# mosaico-dock-schematic.net
KiCad netlist of a schematic drawn in EasyEDA
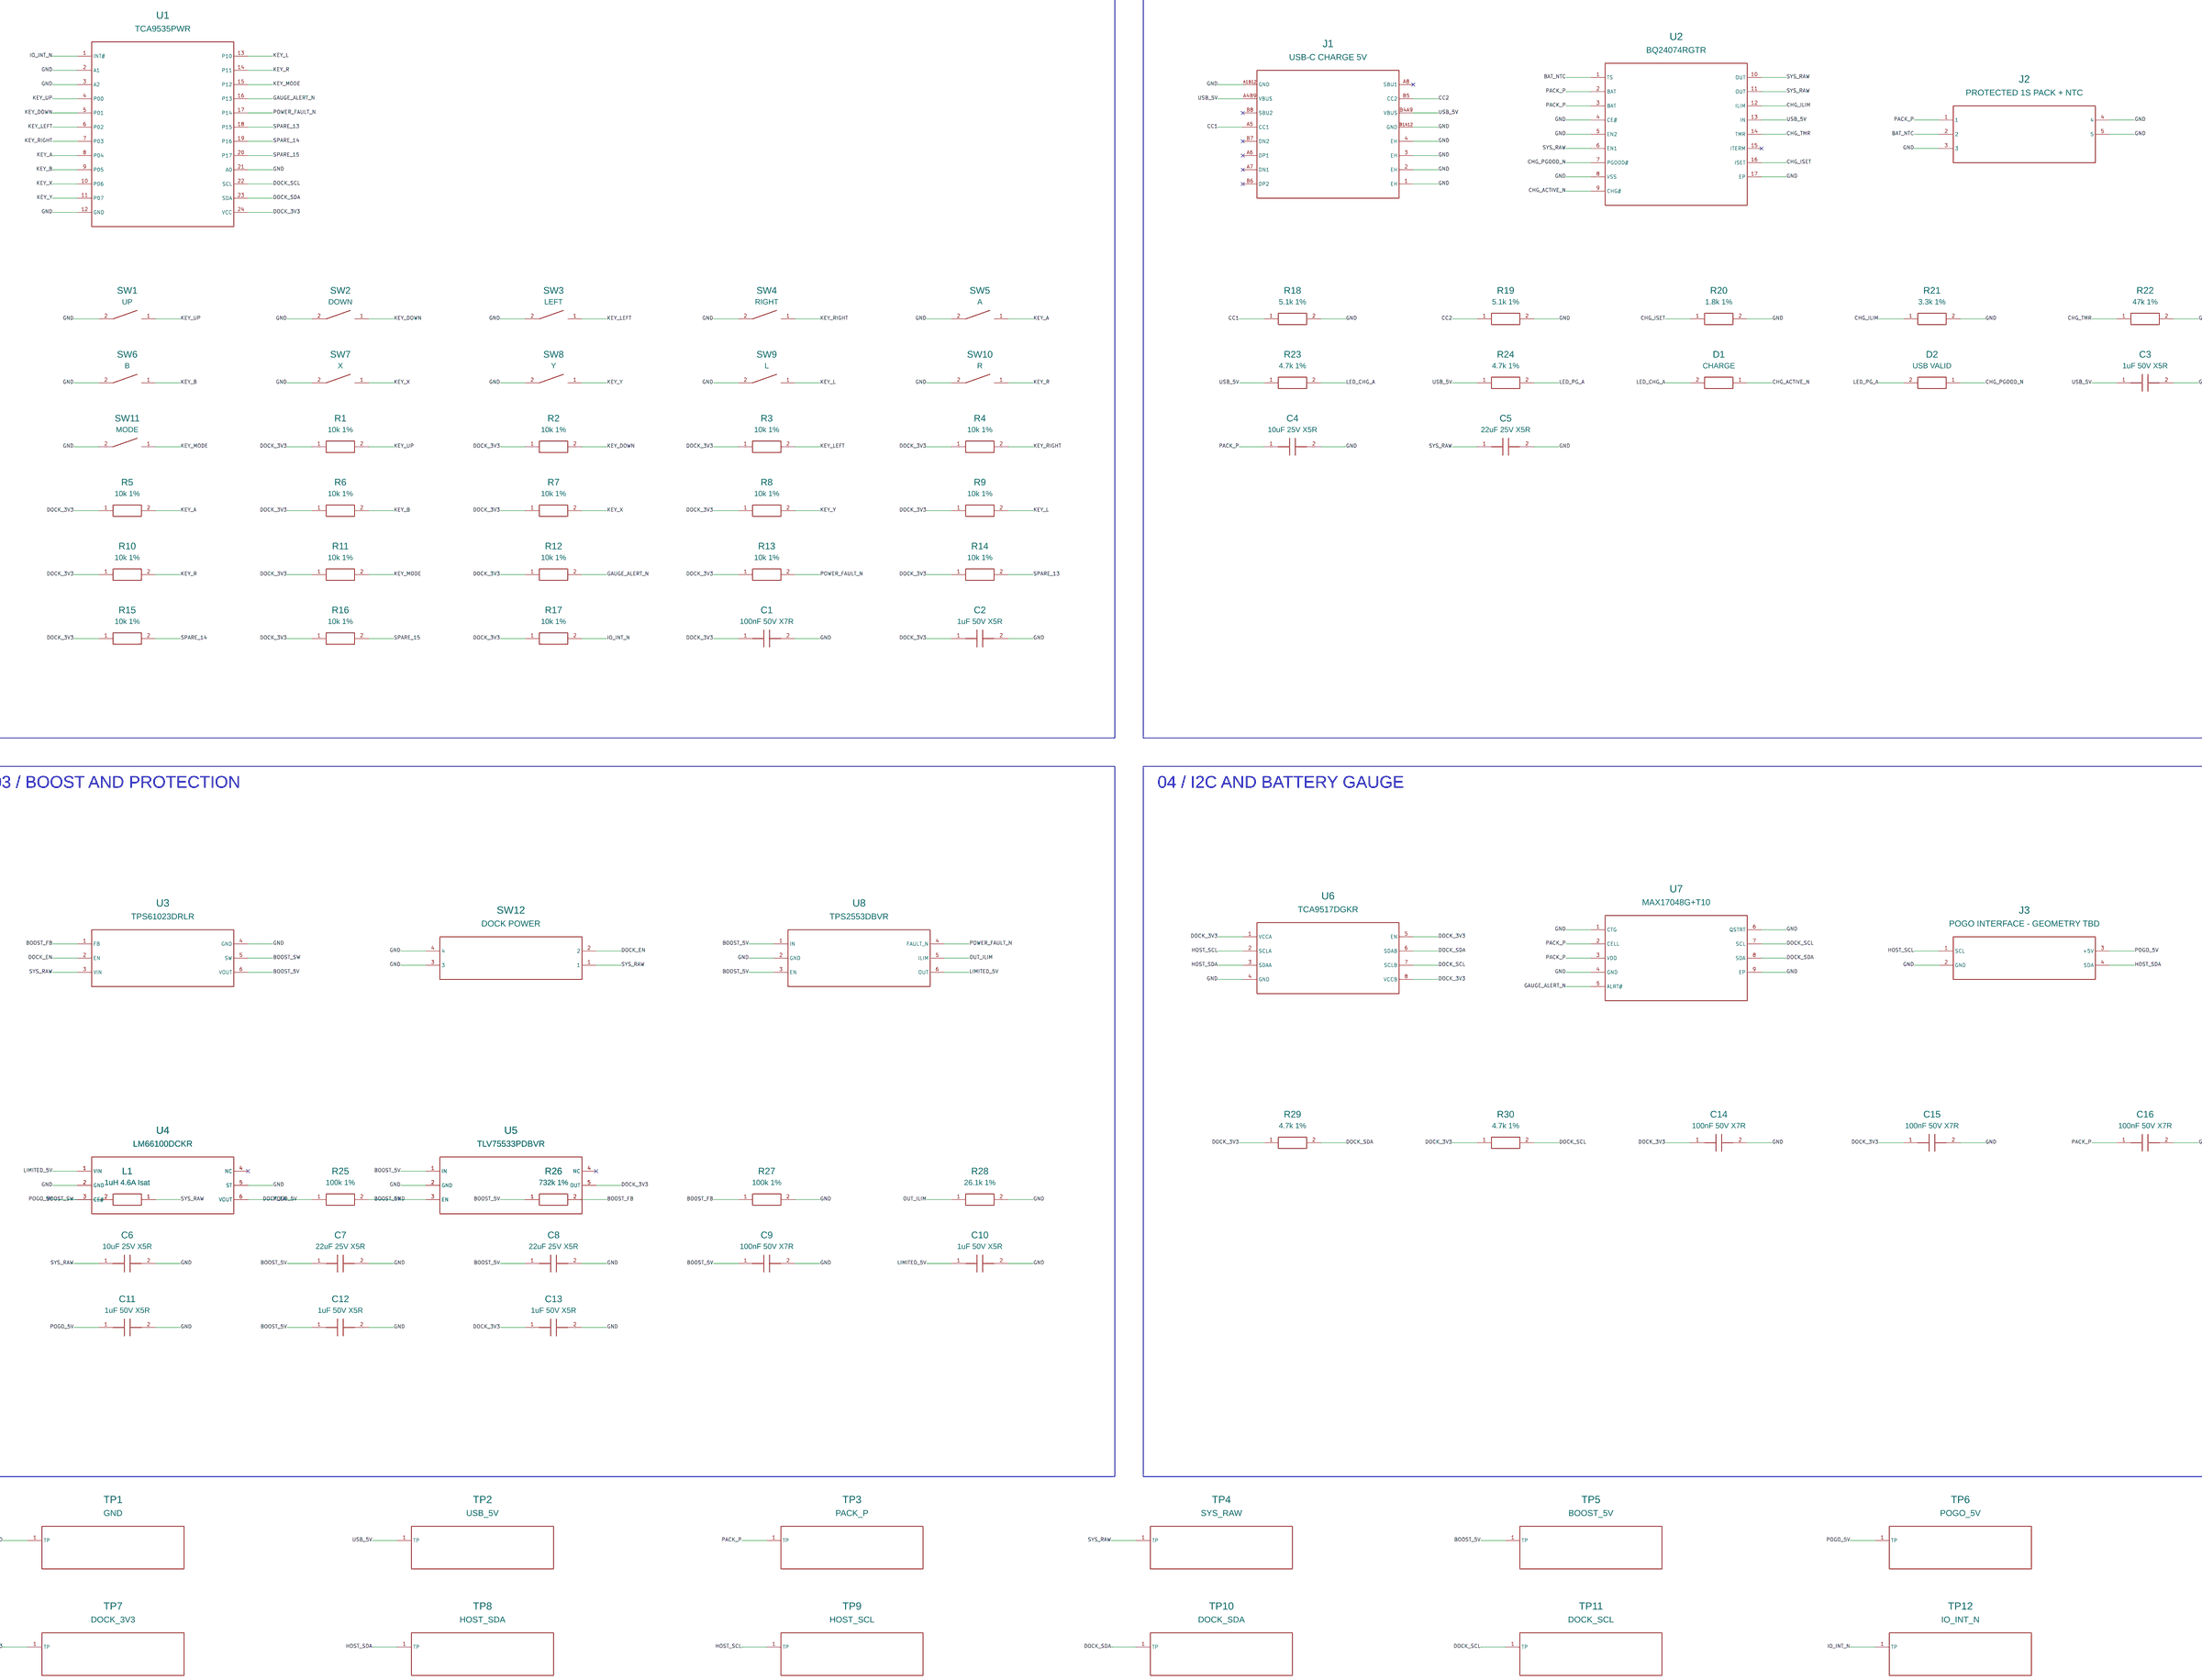
[diagram p0: schematic sheet]

(export (version "E")
  (design (tool "Eeschema 10.0.6"))
  (components
    (comp (ref "C1") (value "100nF 50V X7R") (libsource (lib "") (part "100nF 50V X7R")))
    (comp (ref "C2")
      (value "1uF 50V X5R")
      (fields
        (field (name "Manufacturer Part") "CL10A105KB8NNNC")
        (field (name "Manufacturer") "SAMSUNG(三星)")
      )
      (libsource (lib "") (part "1uF 50V X5R"))
    )
    (comp (ref "C3")
      (value "1uF 50V X5R")
      (fields
        (field (name "Manufacturer Part") "CL10A105KB8NNNC")
        (field (name "Manufacturer") "SAMSUNG(三星)")
      )
      (libsource (lib "") (part "1uF 50V X5R"))
    )
    (comp (ref "C4")
      (value "10uF 25V X5R")
      (fields
        (field (name "Manufacturer Part") "CL10A106MA8NRNC")
        (field (name "Manufacturer") "SAMSUNG(三星)")
      )
      (libsource (lib "") (part "10uF 25V X5R"))
    )
    (comp (ref "C5") (value "22uF 25V X5R") (libsource (lib "") (part "22uF 25V X5R")))
    (comp (ref "C6")
      (value "10uF 25V X5R")
      (fields
        (field (name "Manufacturer Part") "CL10A106MA8NRNC")
        (field (name "Manufacturer") "SAMSUNG(三星)")
      )
      (libsource (lib "") (part "10uF 25V X5R"))
    )
    (comp (ref "C7") (value "22uF 25V X5R") (libsource (lib "") (part "22uF 25V X5R")))
    (comp (ref "C8") (value "22uF 25V X5R") (libsource (lib "") (part "22uF 25V X5R")))
    (comp (ref "C9") (value "100nF 50V X7R") (libsource (lib "") (part "100nF 50V X7R")))
    (comp (ref "C10")
      (value "1uF 50V X5R")
      (fields
        (field (name "Manufacturer Part") "CL10A105KB8NNNC")
        (field (name "Manufacturer") "SAMSUNG(三星)")
      )
      (libsource (lib "") (part "1uF 50V X5R"))
    )
    (comp (ref "C11")
      (value "1uF 50V X5R")
      (fields
        (field (name "Manufacturer Part") "CL10A105KB8NNNC")
        (field (name "Manufacturer") "SAMSUNG(三星)")
      )
      (libsource (lib "") (part "1uF 50V X5R"))
    )
    (comp (ref "C12")
      (value "1uF 50V X5R")
      (fields
        (field (name "Manufacturer Part") "CL10A105KB8NNNC")
        (field (name "Manufacturer") "SAMSUNG(三星)")
      )
      (libsource (lib "") (part "1uF 50V X5R"))
    )
    (comp (ref "C13")
      (value "1uF 50V X5R")
      (fields
        (field (name "Manufacturer Part") "CL10A105KB8NNNC")
        (field (name "Manufacturer") "SAMSUNG(三星)")
      )
      (libsource (lib "") (part "1uF 50V X5R"))
    )
    (comp (ref "C14") (value "100nF 50V X7R") (libsource (lib "") (part "100nF 50V X7R")))
    (comp (ref "C15") (value "100nF 50V X7R") (libsource (lib "") (part "100nF 50V X7R")))
    (comp (ref "C16") (value "100nF 50V X7R") (libsource (lib "") (part "100nF 50V X7R")))
    (comp (ref "D1")
      (value "CHARGE")
      (fields (field (name "Manufacturer Part") "KT-0805黄灯") (field (name "Manufacturer") "KENTO"))
      (libsource (lib "") (part "CHARGE"))
    )
    (comp (ref "D2")
      (value "USB VALID")
      (fields (field (name "Manufacturer Part") "KT-0805黄灯") (field (name "Manufacturer") "KENTO"))
      (libsource (lib "") (part "USB VALID"))
    )
    (comp (ref "J1")
      (value "USB-C CHARGE 5V")
      (fields (field (name "Manufacturer Part") "TYPE-C-31-M-12") (field (name "Manufacturer") "韩国韩荣"))
      (libsource (lib "") (part "USB-C CHARGE 5V"))
    )
    (comp (ref "J2")
      (value "PROTECTED 1S PACK + NTC")
      (fields (field (name "Manufacturer Part") "B3B-PH-SM4-TB(LF)(SN)") (field (name "Manufacturer") "JST"))
      (libsource (lib "") (part "PROTECTED 1S PACK + NTC"))
    )
    (comp (ref "J3")
      (value "POGO INTERFACE - GEOMETRY TBD")
      (libsource (lib "") (part "POGO INTERFACE - GEOMETRY TBD"))
    )
    (comp (ref "L1")
      (value "1uH 4.6A Isat")
      (fields
        (field (name "Manufacturer Part") "FTC201610S1R0MBCA")
        (field (name "Manufacturer") "cjiang(长江微电)")
      )
      (libsource (lib "") (part "1uH 4.6A Isat"))
    )
    (comp (ref "R1")
      (value "10k 1%")
      (fields
        (field (name "Manufacturer Part") "0603WAF1002T5E")
        (field (name "Manufacturer") "UNI-ROYAL(厚声)")
      )
      (libsource (lib "") (part "10k 1%"))
    )
    (comp (ref "R2")
      (value "10k 1%")
      (fields
        (field (name "Manufacturer Part") "0603WAF1002T5E")
        (field (name "Manufacturer") "UNI-ROYAL(厚声)")
      )
      (libsource (lib "") (part "10k 1%"))
    )
    (comp (ref "R3")
      (value "10k 1%")
      (fields
        (field (name "Manufacturer Part") "0603WAF1002T5E")
        (field (name "Manufacturer") "UNI-ROYAL(厚声)")
      )
      (libsource (lib "") (part "10k 1%"))
    )
    (comp (ref "R4")
      (value "10k 1%")
      (fields
        (field (name "Manufacturer Part") "0603WAF1002T5E")
        (field (name "Manufacturer") "UNI-ROYAL(厚声)")
      )
      (libsource (lib "") (part "10k 1%"))
    )
    (comp (ref "R5")
      (value "10k 1%")
      (fields
        (field (name "Manufacturer Part") "0603WAF1002T5E")
        (field (name "Manufacturer") "UNI-ROYAL(厚声)")
      )
      (libsource (lib "") (part "10k 1%"))
    )
    (comp (ref "R6")
      (value "10k 1%")
      (fields
        (field (name "Manufacturer Part") "0603WAF1002T5E")
        (field (name "Manufacturer") "UNI-ROYAL(厚声)")
      )
      (libsource (lib "") (part "10k 1%"))
    )
    (comp (ref "R7")
      (value "10k 1%")
      (fields
        (field (name "Manufacturer Part") "0603WAF1002T5E")
        (field (name "Manufacturer") "UNI-ROYAL(厚声)")
      )
      (libsource (lib "") (part "10k 1%"))
    )
    (comp (ref "R8")
      (value "10k 1%")
      (fields
        (field (name "Manufacturer Part") "0603WAF1002T5E")
        (field (name "Manufacturer") "UNI-ROYAL(厚声)")
      )
      (libsource (lib "") (part "10k 1%"))
    )
    (comp (ref "R9")
      (value "10k 1%")
      (fields
        (field (name "Manufacturer Part") "0603WAF1002T5E")
        (field (name "Manufacturer") "UNI-ROYAL(厚声)")
      )
      (libsource (lib "") (part "10k 1%"))
    )
    (comp (ref "R10")
      (value "10k 1%")
      (fields
        (field (name "Manufacturer Part") "0603WAF1002T5E")
        (field (name "Manufacturer") "UNI-ROYAL(厚声)")
      )
      (libsource (lib "") (part "10k 1%"))
    )
    (comp (ref "R11")
      (value "10k 1%")
      (fields
        (field (name "Manufacturer Part") "0603WAF1002T5E")
        (field (name "Manufacturer") "UNI-ROYAL(厚声)")
      )
      (libsource (lib "") (part "10k 1%"))
    )
    (comp (ref "R12")
      (value "10k 1%")
      (fields
        (field (name "Manufacturer Part") "0603WAF1002T5E")
        (field (name "Manufacturer") "UNI-ROYAL(厚声)")
      )
      (libsource (lib "") (part "10k 1%"))
    )
    (comp (ref "R13")
      (value "10k 1%")
      (fields
        (field (name "Manufacturer Part") "0603WAF1002T5E")
        (field (name "Manufacturer") "UNI-ROYAL(厚声)")
      )
      (libsource (lib "") (part "10k 1%"))
    )
    (comp (ref "R14")
      (value "10k 1%")
      (fields
        (field (name "Manufacturer Part") "0603WAF1002T5E")
        (field (name "Manufacturer") "UNI-ROYAL(厚声)")
      )
      (libsource (lib "") (part "10k 1%"))
    )
    (comp (ref "R15")
      (value "10k 1%")
      (fields
        (field (name "Manufacturer Part") "0603WAF1002T5E")
        (field (name "Manufacturer") "UNI-ROYAL(厚声)")
      )
      (libsource (lib "") (part "10k 1%"))
    )
    (comp (ref "R16")
      (value "10k 1%")
      (fields
        (field (name "Manufacturer Part") "0603WAF1002T5E")
        (field (name "Manufacturer") "UNI-ROYAL(厚声)")
      )
      (libsource (lib "") (part "10k 1%"))
    )
    (comp (ref "R17")
      (value "10k 1%")
      (fields
        (field (name "Manufacturer Part") "0603WAF1002T5E")
        (field (name "Manufacturer") "UNI-ROYAL(厚声)")
      )
      (libsource (lib "") (part "10k 1%"))
    )
    (comp (ref "R18")
      (value "5.1k 1%")
      (fields
        (field (name "Manufacturer Part") "0603WAF5101T5E")
        (field (name "Manufacturer") "UNI-ROYAL(厚声)")
      )
      (libsource (lib "") (part "5.1k 1%"))
    )
    (comp (ref "R19")
      (value "5.1k 1%")
      (fields
        (field (name "Manufacturer Part") "0603WAF5101T5E")
        (field (name "Manufacturer") "UNI-ROYAL(厚声)")
      )
      (libsource (lib "") (part "5.1k 1%"))
    )
    (comp (ref "R20") (value "1.8k 1%") (libsource (lib "") (part "1.8k 1%")))
    (comp (ref "R21") (value "3.3k 1%") (libsource (lib "") (part "3.3k 1%")))
    (comp (ref "R22") (value "47k 1%") (libsource (lib "") (part "47k 1%")))
    (comp (ref "R23")
      (value "4.7k 1%")
      (fields
        (field (name "Manufacturer Part") "0603WAF4701T5E")
        (field (name "Manufacturer") "UNI-ROYAL(厚声)")
      )
      (libsource (lib "") (part "4.7k 1%"))
    )
    (comp (ref "R24")
      (value "4.7k 1%")
      (fields
        (field (name "Manufacturer Part") "0603WAF4701T5E")
        (field (name "Manufacturer") "UNI-ROYAL(厚声)")
      )
      (libsource (lib "") (part "4.7k 1%"))
    )
    (comp (ref "R25")
      (value "100k 1%")
      (fields
        (field (name "Manufacturer Part") "0603WAF1003T5E")
        (field (name "Manufacturer") "UNI-ROYAL(厚声)")
      )
      (libsource (lib "") (part "100k 1%"))
    )
    (comp (ref "R26") (value "732k 1%") (libsource (lib "") (part "732k 1%")))
    (comp (ref "R27")
      (value "100k 1%")
      (fields
        (field (name "Manufacturer Part") "0603WAF1003T5E")
        (field (name "Manufacturer") "UNI-ROYAL(厚声)")
      )
      (libsource (lib "") (part "100k 1%"))
    )
    (comp (ref "R28") (value "26.1k 1%") (libsource (lib "") (part "26.1k 1%")))
    (comp (ref "R29")
      (value "4.7k 1%")
      (fields
        (field (name "Manufacturer Part") "0603WAF4701T5E")
        (field (name "Manufacturer") "UNI-ROYAL(厚声)")
      )
      (libsource (lib "") (part "4.7k 1%"))
    )
    (comp (ref "R30")
      (value "4.7k 1%")
      (fields
        (field (name "Manufacturer Part") "0603WAF4701T5E")
        (field (name "Manufacturer") "UNI-ROYAL(厚声)")
      )
      (libsource (lib "") (part "4.7k 1%"))
    )
    (comp (ref "SW1")
      (value "UP")
      (fields (field (name "Manufacturer Part") "TS-1088-AR02016") (field (name "Manufacturer") "XUNPU(讯普)"))
      (libsource (lib "") (part "UP"))
    )
    (comp (ref "SW2")
      (value "DOWN")
      (fields (field (name "Manufacturer Part") "TS-1088-AR02016") (field (name "Manufacturer") "XUNPU(讯普)"))
      (libsource (lib "") (part "DOWN"))
    )
    (comp (ref "SW3")
      (value "LEFT")
      (fields (field (name "Manufacturer Part") "TS-1088-AR02016") (field (name "Manufacturer") "XUNPU(讯普)"))
      (libsource (lib "") (part "LEFT"))
    )
    (comp (ref "SW4")
      (value "RIGHT")
      (fields (field (name "Manufacturer Part") "TS-1088-AR02016") (field (name "Manufacturer") "XUNPU(讯普)"))
      (libsource (lib "") (part "RIGHT"))
    )
    (comp (ref "SW5")
      (value "A")
      (fields (field (name "Manufacturer Part") "TS-1088-AR02016") (field (name "Manufacturer") "XUNPU(讯普)"))
      (libsource (lib "") (part "A"))
    )
    (comp (ref "SW6")
      (value "B")
      (fields (field (name "Manufacturer Part") "TS-1088-AR02016") (field (name "Manufacturer") "XUNPU(讯普)"))
      (libsource (lib "") (part "B"))
    )
    (comp (ref "SW7")
      (value "X")
      (fields (field (name "Manufacturer Part") "TS-1088-AR02016") (field (name "Manufacturer") "XUNPU(讯普)"))
      (libsource (lib "") (part "X"))
    )
    (comp (ref "SW8")
      (value "Y")
      (fields (field (name "Manufacturer Part") "TS-1088-AR02016") (field (name "Manufacturer") "XUNPU(讯普)"))
      (libsource (lib "") (part "Y"))
    )
    (comp (ref "SW9")
      (value "L")
      (fields (field (name "Manufacturer Part") "TS-1088-AR02016") (field (name "Manufacturer") "XUNPU(讯普)"))
      (libsource (lib "") (part "L"))
    )
    (comp (ref "SW10")
      (value "R")
      (fields (field (name "Manufacturer Part") "TS-1088-AR02016") (field (name "Manufacturer") "XUNPU(讯普)"))
      (libsource (lib "") (part "R"))
    )
    (comp (ref "SW11")
      (value "MODE")
      (fields (field (name "Manufacturer Part") "TS-1088-AR02016") (field (name "Manufacturer") "XUNPU(讯普)"))
      (libsource (lib "") (part "MODE"))
    )
    (comp (ref "SW12")
      (value "DOCK POWER")
      (fields (field (name "Manufacturer Part") "MSK12C02") (field (name "Manufacturer") "SHOU HAN(首韩)"))
      (libsource (lib "") (part "DOCK POWER"))
    )
    (comp (ref "TP1") (value "GND") (libsource (lib "") (part "GND")))
    (comp (ref "TP2") (value "USB_5V") (libsource (lib "") (part "USB_5V")))
    (comp (ref "TP3") (value "PACK_P") (libsource (lib "") (part "PACK_P")))
    (comp (ref "TP4") (value "SYS_RAW") (libsource (lib "") (part "SYS_RAW")))
    (comp (ref "TP5") (value "BOOST_5V") (libsource (lib "") (part "BOOST_5V")))
    (comp (ref "TP6") (value "POGO_5V") (libsource (lib "") (part "POGO_5V")))
    (comp (ref "TP7") (value "DOCK_3V3") (libsource (lib "") (part "DOCK_3V3")))
    (comp (ref "TP8") (value "HOST_SDA") (libsource (lib "") (part "HOST_SDA")))
    (comp (ref "TP9") (value "HOST_SCL") (libsource (lib "") (part "HOST_SCL")))
    (comp (ref "TP10") (value "DOCK_SDA") (libsource (lib "") (part "DOCK_SDA")))
    (comp (ref "TP11") (value "DOCK_SCL") (libsource (lib "") (part "DOCK_SCL")))
    (comp (ref "TP12") (value "IO_INT_N") (libsource (lib "") (part "IO_INT_N")))
    (comp (ref "U1")
      (value "TCA9535PWR")
      (fields (field (name "Manufacturer") "TI(德州仪器)"))
      (libsource (lib "") (part "TCA9535PWR"))
    )
    (comp (ref "U2")
      (value "BQ24074RGTR")
      (fields (field (name "Manufacturer") "TI(德州仪器)"))
      (libsource (lib "") (part "BQ24074RGTR"))
    )
    (comp (ref "U3")
      (value "TPS61023DRLR")
      (fields (field (name "Manufacturer") "TI(德州仪器)"))
      (libsource (lib "") (part "TPS61023DRLR"))
    )
    (comp (ref "U4")
      (value "LM66100DCKR")
      (fields (field (name "Manufacturer") "TI(德州仪器)"))
      (libsource (lib "") (part "LM66100DCKR"))
    )
    (comp (ref "U5")
      (value "TLV75533PDBVR")
      (fields (field (name "Manufacturer") "TI(德州仪器)"))
      (libsource (lib "") (part "TLV75533PDBVR"))
    )
    (comp (ref "U6")
      (value "TCA9517DGKR")
      (fields (field (name "Manufacturer") "TI(德州仪器)"))
      (libsource (lib "") (part "TCA9517DGKR"))
    )
    (comp (ref "U7")
      (value "MAX17048G+T10")
      (fields (field (name "Manufacturer") "ADI(亚德诺)/MAXIM(美信)"))
      (libsource (lib "") (part "MAX17048G+T10"))
    )
    (comp (ref "U8") (value "TPS2553DBVR") (libsource (lib "") (part "TPS2553DBVR")))
  )
  (nets
    (net (code "1") (name "/BAT_NTC") (class "Default")
      (node (ref "J2") (pin "2") (pinfunction "2_2") (pintype "unspecified"))
      (node (ref "U2") (pin "1") (pinfunction "TS_1") (pintype "unspecified"))
    )
    (net (code "2") (name "/BOOST_5V") (class "Default")
      (node (ref "C12") (pin "1") (pintype "unspecified"))
      (node (ref "C7") (pin "1") (pintype "unspecified"))
      (node (ref "C8") (pin "1") (pintype "unspecified"))
      (node (ref "C9") (pin "1") (pintype "unspecified"))
      (node (ref "R26") (pin "1") (pintype "unspecified"))
      (node (ref "TP5") (pin "1") (pinfunction "TP_1") (pintype "unspecified"))
      (node (ref "U3") (pin "6") (pinfunction "VOUT_6") (pintype "unspecified"))
      (node (ref "U5") (pin "1") (pinfunction "IN_1") (pintype "unspecified"))
      (node (ref "U5") (pin "3") (pinfunction "EN_3") (pintype "unspecified"))
      (node (ref "U8") (pin "1") (pinfunction "IN_1") (pintype "unspecified"))
      (node (ref "U8") (pin "3") (pinfunction "EN_3") (pintype "unspecified"))
    )
    (net (code "3") (name "/BOOST_FB") (class "Default")
      (node (ref "R26") (pin "2") (pintype "unspecified"))
      (node (ref "R27") (pin "1") (pintype "unspecified"))
      (node (ref "U3") (pin "1") (pinfunction "FB_1") (pintype "unspecified"))
    )
    (net (code "4") (name "/BOOST_SW") (class "Default")
      (node (ref "C11") (pin "1") (pintype "unspecified"))
      (node (ref "J3") (pin "3") (pinfunction "+5V_3") (pintype "unspecified"))
      (node (ref "L1") (pin "2") (pintype "unspecified"))
      (node (ref "TP6") (pin "1") (pinfunction "TP_1") (pintype "unspecified"))
      (node (ref "U3") (pin "5") (pinfunction "SW_5") (pintype "unspecified"))
      (node (ref "U4") (pin "3") (pinfunction "CE#_3") (pintype "unspecified"))
      (node (ref "U4") (pin "6") (pinfunction "VOUT_6") (pintype "unspecified"))
    )
    (net (code "5") (name "/CC1") (class "Default")
      (node (ref "J1") (pin "A5") (pinfunction "CC1_A5") (pintype "unspecified"))
      (node (ref "R18") (pin "1") (pintype "unspecified"))
    )
    (net (code "6") (name "/CC2") (class "Default")
      (node (ref "J1") (pin "B5") (pinfunction "CC2_B5") (pintype "unspecified"))
      (node (ref "R19") (pin "1") (pintype "unspecified"))
    )
    (net (code "7") (name "/CHG_ACTIVE_N") (class "Default")
      (node (ref "D1") (pin "1") (pintype "unspecified"))
      (node (ref "U2") (pin "9") (pinfunction "CHG#_9") (pintype "unspecified"))
    )
    (net (code "8") (name "/CHG_ILIM") (class "Default")
      (node (ref "R21") (pin "1") (pintype "unspecified"))
      (node (ref "U2") (pin "12") (pinfunction "ILIM_12") (pintype "unspecified"))
    )
    (net (code "9") (name "/CHG_ISET") (class "Default")
      (node (ref "R20") (pin "1") (pintype "unspecified"))
      (node (ref "U2") (pin "16") (pinfunction "ISET_16") (pintype "unspecified"))
    )
    (net (code "10") (name "/CHG_PGOOD_N") (class "Default")
      (node (ref "D2") (pin "1") (pintype "unspecified"))
      (node (ref "U2") (pin "7") (pinfunction "PGOOD#_7") (pintype "unspecified"))
    )
    (net (code "11") (name "/CHG_TMR") (class "Default")
      (node (ref "R22") (pin "1") (pintype "unspecified"))
      (node (ref "U2") (pin "14") (pinfunction "TMR_14") (pintype "unspecified"))
    )
    (net (code "12") (name "/DOCK_3V3") (class "Default")
      (node (ref "C1") (pin "1") (pintype "unspecified"))
      (node (ref "C13") (pin "1") (pintype "unspecified"))
      (node (ref "C14") (pin "1") (pintype "unspecified"))
      (node (ref "C15") (pin "1") (pintype "unspecified"))
      (node (ref "C2") (pin "1") (pintype "unspecified"))
      (node (ref "R1") (pin "1") (pintype "unspecified"))
      (node (ref "R10") (pin "1") (pintype "unspecified"))
      (node (ref "R11") (pin "1") (pintype "unspecified"))
      (node (ref "R12") (pin "1") (pintype "unspecified"))
      (node (ref "R13") (pin "1") (pintype "unspecified"))
      (node (ref "R14") (pin "1") (pintype "unspecified"))
      (node (ref "R15") (pin "1") (pintype "unspecified"))
      (node (ref "R16") (pin "1") (pintype "unspecified"))
      (node (ref "R17") (pin "1") (pintype "unspecified"))
      (node (ref "R2") (pin "1") (pintype "unspecified"))
      (node (ref "R29") (pin "1") (pintype "unspecified"))
      (node (ref "R3") (pin "1") (pintype "unspecified"))
      (node (ref "R30") (pin "1") (pintype "unspecified"))
      (node (ref "R4") (pin "1") (pintype "unspecified"))
      (node (ref "R5") (pin "1") (pintype "unspecified"))
      (node (ref "R6") (pin "1") (pintype "unspecified"))
      (node (ref "R7") (pin "1") (pintype "unspecified"))
      (node (ref "R8") (pin "1") (pintype "unspecified"))
      (node (ref "R9") (pin "1") (pintype "unspecified"))
      (node (ref "TP7") (pin "1") (pinfunction "TP_1") (pintype "unspecified"))
      (node (ref "U1") (pin "24") (pinfunction "VCC_24") (pintype "unspecified"))
      (node (ref "U5") (pin "5") (pinfunction "OUT_5") (pintype "unspecified"))
      (node (ref "U6") (pin "1") (pinfunction "VCCA_1") (pintype "unspecified"))
      (node (ref "U6") (pin "5") (pinfunction "EN_5") (pintype "unspecified"))
      (node (ref "U6") (pin "8") (pinfunction "VCCB_8") (pintype "unspecified"))
    )
    (net (code "13") (name "/DOCK_EN") (class "Default")
      (node (ref "R25") (pin "1") (pintype "unspecified"))
      (node (ref "SW12") (pin "2") (pinfunction "2_2") (pintype "unspecified"))
      (node (ref "U3") (pin "2") (pinfunction "EN_2") (pintype "unspecified"))
    )
    (net (code "14") (name "/DOCK_SCL") (class "Default")
      (node (ref "R30") (pin "2") (pintype "unspecified"))
      (node (ref "TP11") (pin "1") (pinfunction "TP_1") (pintype "unspecified"))
      (node (ref "U1") (pin "22") (pinfunction "SCL_22") (pintype "unspecified"))
      (node (ref "U6") (pin "7") (pinfunction "SCLB_7") (pintype "unspecified"))
      (node (ref "U7") (pin "7") (pinfunction "SCL_7") (pintype "unspecified"))
    )
    (net (code "15") (name "/DOCK_SDA") (class "Default")
      (node (ref "R29") (pin "2") (pintype "unspecified"))
      (node (ref "TP10") (pin "1") (pinfunction "TP_1") (pintype "unspecified"))
      (node (ref "U1") (pin "23") (pinfunction "SDA_23") (pintype "unspecified"))
      (node (ref "U6") (pin "6") (pinfunction "SDAB_6") (pintype "unspecified"))
      (node (ref "U7") (pin "8") (pinfunction "SDA_8") (pintype "unspecified"))
    )
    (net (code "16") (name "/GAUGE_ALERT_N") (class "Default")
      (node (ref "R12") (pin "2") (pintype "unspecified"))
      (node (ref "U1") (pin "16") (pinfunction "P13_16") (pintype "unspecified"))
      (node (ref "U7") (pin "5") (pinfunction "ALRT#_5") (pintype "unspecified"))
    )
    (net (code "17") (name "/GND") (class "Default")
      (node (ref "C1") (pin "2") (pintype "unspecified"))
      (node (ref "C10") (pin "2") (pintype "unspecified"))
      (node (ref "C11") (pin "2") (pintype "unspecified"))
      (node (ref "C12") (pin "2") (pintype "unspecified"))
      (node (ref "C13") (pin "2") (pintype "unspecified"))
      (node (ref "C14") (pin "2") (pintype "unspecified"))
      (node (ref "C15") (pin "2") (pintype "unspecified"))
      (node (ref "C16") (pin "2") (pintype "unspecified"))
      (node (ref "C2") (pin "2") (pintype "unspecified"))
      (node (ref "C3") (pin "2") (pintype "unspecified"))
      (node (ref "C4") (pin "2") (pintype "unspecified"))
      (node (ref "C5") (pin "2") (pintype "unspecified"))
      (node (ref "C6") (pin "2") (pintype "unspecified"))
      (node (ref "C7") (pin "2") (pintype "unspecified"))
      (node (ref "C8") (pin "2") (pintype "unspecified"))
      (node (ref "C9") (pin "2") (pintype "unspecified"))
      (node (ref "J1") (pin "1") (pinfunction "EH_1") (pintype "unspecified"))
      (node (ref "J1") (pin "2") (pinfunction "EH_2") (pintype "unspecified"))
      (node (ref "J1") (pin "3") (pinfunction "EH_3") (pintype "unspecified"))
      (node (ref "J1") (pin "4") (pinfunction "EH_4") (pintype "unspecified"))
      (node (ref "J1") (pin "A1B12") (pinfunction "GND_A1B12") (pintype "unspecified"))
      (node (ref "J1") (pin "B1A12") (pinfunction "GND_B1A12") (pintype "unspecified"))
      (node (ref "J2") (pin "3") (pinfunction "3_3") (pintype "unspecified"))
      (node (ref "J2") (pin "4") (pinfunction "4_4") (pintype "unspecified"))
      (node (ref "J2") (pin "5") (pinfunction "5_5") (pintype "unspecified"))
      (node (ref "J3") (pin "2") (pinfunction "GND_2") (pintype "unspecified"))
      (node (ref "R18") (pin "2") (pintype "unspecified"))
      (node (ref "R19") (pin "2") (pintype "unspecified"))
      (node (ref "R20") (pin "2") (pintype "unspecified"))
      (node (ref "R21") (pin "2") (pintype "unspecified"))
      (node (ref "R22") (pin "2") (pintype "unspecified"))
      (node (ref "R25") (pin "2") (pintype "unspecified"))
      (node (ref "R27") (pin "2") (pintype "unspecified"))
      (node (ref "R28") (pin "2") (pintype "unspecified"))
      (node (ref "SW1") (pin "2") (pintype "unspecified"))
      (node (ref "SW10") (pin "2") (pintype "unspecified"))
      (node (ref "SW11") (pin "2") (pintype "unspecified"))
      (node (ref "SW12") (pin "3") (pinfunction "3_3") (pintype "unspecified"))
      (node (ref "SW12") (pin "4") (pinfunction "4_4") (pintype "unspecified"))
      (node (ref "SW2") (pin "2") (pintype "unspecified"))
      (node (ref "SW3") (pin "2") (pintype "unspecified"))
      (node (ref "SW4") (pin "2") (pintype "unspecified"))
      (node (ref "SW5") (pin "2") (pintype "unspecified"))
      (node (ref "SW6") (pin "2") (pintype "unspecified"))
      (node (ref "SW7") (pin "2") (pintype "unspecified"))
      (node (ref "SW8") (pin "2") (pintype "unspecified"))
      (node (ref "SW9") (pin "2") (pintype "unspecified"))
      (node (ref "TP1") (pin "1") (pinfunction "TP_1") (pintype "unspecified"))
      (node (ref "U1") (pin "12") (pinfunction "GND_12") (pintype "unspecified"))
      (node (ref "U1") (pin "2") (pinfunction "A1_2") (pintype "unspecified"))
      (node (ref "U1") (pin "21") (pinfunction "A0_21") (pintype "unspecified"))
      (node (ref "U1") (pin "3") (pinfunction "A2_3") (pintype "unspecified"))
      (node (ref "U2") (pin "17") (pinfunction "EP_17") (pintype "unspecified"))
      (node (ref "U2") (pin "4") (pinfunction "CE#_4") (pintype "unspecified"))
      (node (ref "U2") (pin "5") (pinfunction "EN2_5") (pintype "unspecified"))
      (node (ref "U2") (pin "8") (pinfunction "VSS_8") (pintype "unspecified"))
      (node (ref "U3") (pin "4") (pinfunction "GND_4") (pintype "unspecified"))
      (node (ref "U4") (pin "2") (pinfunction "GND_2") (pintype "unspecified"))
      (node (ref "U4") (pin "5") (pinfunction "ST_5") (pintype "unspecified"))
      (node (ref "U5") (pin "2") (pinfunction "GND_2") (pintype "unspecified"))
      (node (ref "U6") (pin "4") (pinfunction "GND_4") (pintype "unspecified"))
      (node (ref "U7") (pin "1") (pinfunction "CTG_1") (pintype "unspecified"))
      (node (ref "U7") (pin "4") (pinfunction "GND_4") (pintype "unspecified"))
      (node (ref "U7") (pin "6") (pinfunction "QSTRT_6") (pintype "unspecified"))
      (node (ref "U7") (pin "9") (pinfunction "EP_9") (pintype "unspecified"))
      (node (ref "U8") (pin "2") (pinfunction "GND_2") (pintype "unspecified"))
    )
    (net (code "18") (name "/HOST_SCL") (class "Default")
      (node (ref "J3") (pin "1") (pinfunction "SCL_1") (pintype "unspecified"))
      (node (ref "TP9") (pin "1") (pinfunction "TP_1") (pintype "unspecified"))
      (node (ref "U6") (pin "2") (pinfunction "SCLA_2") (pintype "unspecified"))
    )
    (net (code "19") (name "/HOST_SDA") (class "Default")
      (node (ref "J3") (pin "4") (pinfunction "SDA_4") (pintype "unspecified"))
      (node (ref "TP8") (pin "1") (pinfunction "TP_1") (pintype "unspecified"))
      (node (ref "U6") (pin "3") (pinfunction "SDAA_3") (pintype "unspecified"))
    )
    (net (code "20") (name "/IO_INT_N") (class "Default")
      (node (ref "R17") (pin "2") (pintype "unspecified"))
      (node (ref "TP12") (pin "1") (pinfunction "TP_1") (pintype "unspecified"))
      (node (ref "U1") (pin "1") (pinfunction "INT#_1") (pintype "unspecified"))
    )
    (net (code "21") (name "/KEY_A") (class "Default")
      (node (ref "R5") (pin "2") (pintype "unspecified"))
      (node (ref "SW5") (pin "1") (pintype "unspecified"))
      (node (ref "U1") (pin "8") (pinfunction "P04_8") (pintype "unspecified"))
    )
    (net (code "22") (name "/KEY_B") (class "Default")
      (node (ref "R6") (pin "2") (pintype "unspecified"))
      (node (ref "SW6") (pin "1") (pintype "unspecified"))
      (node (ref "U1") (pin "9") (pinfunction "P05_9") (pintype "unspecified"))
    )
    (net (code "23") (name "/KEY_DOWN") (class "Default")
      (node (ref "R2") (pin "2") (pintype "unspecified"))
      (node (ref "SW2") (pin "1") (pintype "unspecified"))
      (node (ref "U1") (pin "5") (pinfunction "P01_5") (pintype "unspecified"))
    )
    (net (code "24") (name "/KEY_L") (class "Default")
      (node (ref "R9") (pin "2") (pintype "unspecified"))
      (node (ref "SW9") (pin "1") (pintype "unspecified"))
      (node (ref "U1") (pin "13") (pinfunction "P10_13") (pintype "unspecified"))
    )
    (net (code "25") (name "/KEY_LEFT") (class "Default")
      (node (ref "R3") (pin "2") (pintype "unspecified"))
      (node (ref "SW3") (pin "1") (pintype "unspecified"))
      (node (ref "U1") (pin "6") (pinfunction "P02_6") (pintype "unspecified"))
    )
    (net (code "26") (name "/KEY_MODE") (class "Default")
      (node (ref "R11") (pin "2") (pintype "unspecified"))
      (node (ref "SW11") (pin "1") (pintype "unspecified"))
      (node (ref "U1") (pin "15") (pinfunction "P12_15") (pintype "unspecified"))
    )
    (net (code "27") (name "/KEY_R") (class "Default")
      (node (ref "R10") (pin "2") (pintype "unspecified"))
      (node (ref "SW10") (pin "1") (pintype "unspecified"))
      (node (ref "U1") (pin "14") (pinfunction "P11_14") (pintype "unspecified"))
    )
    (net (code "28") (name "/KEY_RIGHT") (class "Default")
      (node (ref "R4") (pin "2") (pintype "unspecified"))
      (node (ref "SW4") (pin "1") (pintype "unspecified"))
      (node (ref "U1") (pin "7") (pinfunction "P03_7") (pintype "unspecified"))
    )
    (net (code "29") (name "/KEY_UP") (class "Default")
      (node (ref "R1") (pin "2") (pintype "unspecified"))
      (node (ref "SW1") (pin "1") (pintype "unspecified"))
      (node (ref "U1") (pin "4") (pinfunction "P00_4") (pintype "unspecified"))
    )
    (net (code "30") (name "/KEY_X") (class "Default")
      (node (ref "R7") (pin "2") (pintype "unspecified"))
      (node (ref "SW7") (pin "1") (pintype "unspecified"))
      (node (ref "U1") (pin "10") (pinfunction "P06_10") (pintype "unspecified"))
    )
    (net (code "31") (name "/KEY_Y") (class "Default")
      (node (ref "R8") (pin "2") (pintype "unspecified"))
      (node (ref "SW8") (pin "1") (pintype "unspecified"))
      (node (ref "U1") (pin "11") (pinfunction "P07_11") (pintype "unspecified"))
    )
    (net (code "32") (name "/LED_CHG_A") (class "Default")
      (node (ref "D1") (pin "2") (pintype "unspecified"))
      (node (ref "R23") (pin "2") (pintype "unspecified"))
    )
    (net (code "33") (name "/LED_PG_A") (class "Default")
      (node (ref "D2") (pin "2") (pintype "unspecified"))
      (node (ref "R24") (pin "2") (pintype "unspecified"))
    )
    (net (code "34") (name "/LIMITED_5V") (class "Default")
      (node (ref "C10") (pin "1") (pintype "unspecified"))
      (node (ref "U4") (pin "1") (pinfunction "VIN_1") (pintype "unspecified"))
      (node (ref "U8") (pin "6") (pinfunction "OUT_6") (pintype "unspecified"))
    )
    (net (code "35") (name "/OUT_ILIM") (class "Default")
      (node (ref "R28") (pin "1") (pintype "unspecified"))
      (node (ref "U8") (pin "5") (pinfunction "ILIM_5") (pintype "unspecified"))
    )
    (net (code "36") (name "/PACK_P") (class "Default")
      (node (ref "C16") (pin "1") (pintype "unspecified"))
      (node (ref "C4") (pin "1") (pintype "unspecified"))
      (node (ref "J2") (pin "1") (pinfunction "1_1") (pintype "unspecified"))
      (node (ref "TP3") (pin "1") (pinfunction "TP_1") (pintype "unspecified"))
      (node (ref "U2") (pin "2") (pinfunction "BAT_2") (pintype "unspecified"))
      (node (ref "U2") (pin "3") (pinfunction "BAT_3") (pintype "unspecified"))
      (node (ref "U7") (pin "2") (pinfunction "CELL_2") (pintype "unspecified"))
      (node (ref "U7") (pin "3") (pinfunction "VDD_3") (pintype "unspecified"))
    )
    (net (code "37") (name "/POWER_FAULT_N") (class "Default")
      (node (ref "R13") (pin "2") (pintype "unspecified"))
      (node (ref "U1") (pin "17") (pinfunction "P14_17") (pintype "unspecified"))
      (node (ref "U8") (pin "4") (pinfunction "FAULT_N_4") (pintype "unspecified"))
    )
    (net (code "38") (name "/SPARE_13") (class "Default")
      (node (ref "R14") (pin "2") (pintype "unspecified"))
      (node (ref "U1") (pin "18") (pinfunction "P15_18") (pintype "unspecified"))
    )
    (net (code "39") (name "/SPARE_14") (class "Default")
      (node (ref "R15") (pin "2") (pintype "unspecified"))
      (node (ref "U1") (pin "19") (pinfunction "P16_19") (pintype "unspecified"))
    )
    (net (code "40") (name "/SPARE_15") (class "Default")
      (node (ref "R16") (pin "2") (pintype "unspecified"))
      (node (ref "U1") (pin "20") (pinfunction "P17_20") (pintype "unspecified"))
    )
    (net (code "41") (name "/SYS_RAW") (class "Default")
      (node (ref "C5") (pin "1") (pintype "unspecified"))
      (node (ref "C6") (pin "1") (pintype "unspecified"))
      (node (ref "L1") (pin "1") (pintype "unspecified"))
      (node (ref "SW12") (pin "1") (pinfunction "1_1") (pintype "unspecified"))
      (node (ref "TP4") (pin "1") (pinfunction "TP_1") (pintype "unspecified"))
      (node (ref "U2") (pin "10") (pinfunction "OUT_10") (pintype "unspecified"))
      (node (ref "U2") (pin "11") (pinfunction "OUT_11") (pintype "unspecified"))
      (node (ref "U2") (pin "6") (pinfunction "EN1_6") (pintype "unspecified"))
      (node (ref "U3") (pin "3") (pinfunction "VIN_3") (pintype "unspecified"))
    )
    (net (code "42") (name "/USB_5V") (class "Default")
      (node (ref "C3") (pin "1") (pintype "unspecified"))
      (node (ref "J1") (pin "A4B9") (pinfunction "VBUS_A4B9") (pintype "unspecified"))
      (node (ref "J1") (pin "B4A9") (pinfunction "VBUS_B4A9") (pintype "unspecified"))
      (node (ref "R23") (pin "1") (pintype "unspecified"))
      (node (ref "R24") (pin "1") (pintype "unspecified"))
      (node (ref "TP2") (pin "1") (pinfunction "TP_1") (pintype "unspecified"))
      (node (ref "U2") (pin "13") (pinfunction "IN_13") (pintype "unspecified"))
    )
    (net (code "43") (name "unconnected-(J1-DN1-PadA7)") (class "Default")
      (node (ref "J1") (pin "A7") (pinfunction "DN1_A7") (pintype "unspecified+no_connect"))
    )
    (net (code "44") (name "unconnected-(J1-DN2-PadB7)") (class "Default")
      (node (ref "J1") (pin "B7") (pinfunction "DN2_B7") (pintype "unspecified+no_connect"))
    )
    (net (code "45") (name "unconnected-(J1-DP1-PadA6)") (class "Default")
      (node (ref "J1") (pin "A6") (pinfunction "DP1_A6") (pintype "unspecified+no_connect"))
    )
    (net (code "46") (name "unconnected-(J1-DP2-PadB6)") (class "Default")
      (node (ref "J1") (pin "B6") (pinfunction "DP2_B6") (pintype "unspecified+no_connect"))
    )
    (net (code "47") (name "unconnected-(J1-SBU1-PadA8)") (class "Default")
      (node (ref "J1") (pin "A8") (pinfunction "SBU1_A8") (pintype "unspecified+no_connect"))
    )
    (net (code "48") (name "unconnected-(J1-SBU2-PadB8)") (class "Default")
      (node (ref "J1") (pin "B8") (pinfunction "SBU2_B8") (pintype "unspecified+no_connect"))
    )
    (net (code "49") (name "unconnected-(U2-ITERM-Pad15)") (class "Default")
      (node (ref "U2") (pin "15") (pinfunction "ITERM_15") (pintype "unspecified+no_connect"))
    )
    (net (code "50") (name "unconnected-(U4-NC-Pad4)") (class "Default")
      (node (ref "U4") (pin "4") (pinfunction "NC_4") (pintype "unspecified+no_connect"))
    )
    (net (code "51") (name "unconnected-(U5-NC-Pad4)") (class "Default")
      (node (ref "U5") (pin "4") (pinfunction "NC_4") (pintype "unspecified+no_connect"))
    )
  )
)
